# 468323_001_Encoder.net
KiCad netlist of a schematic drawn in Altium Designer
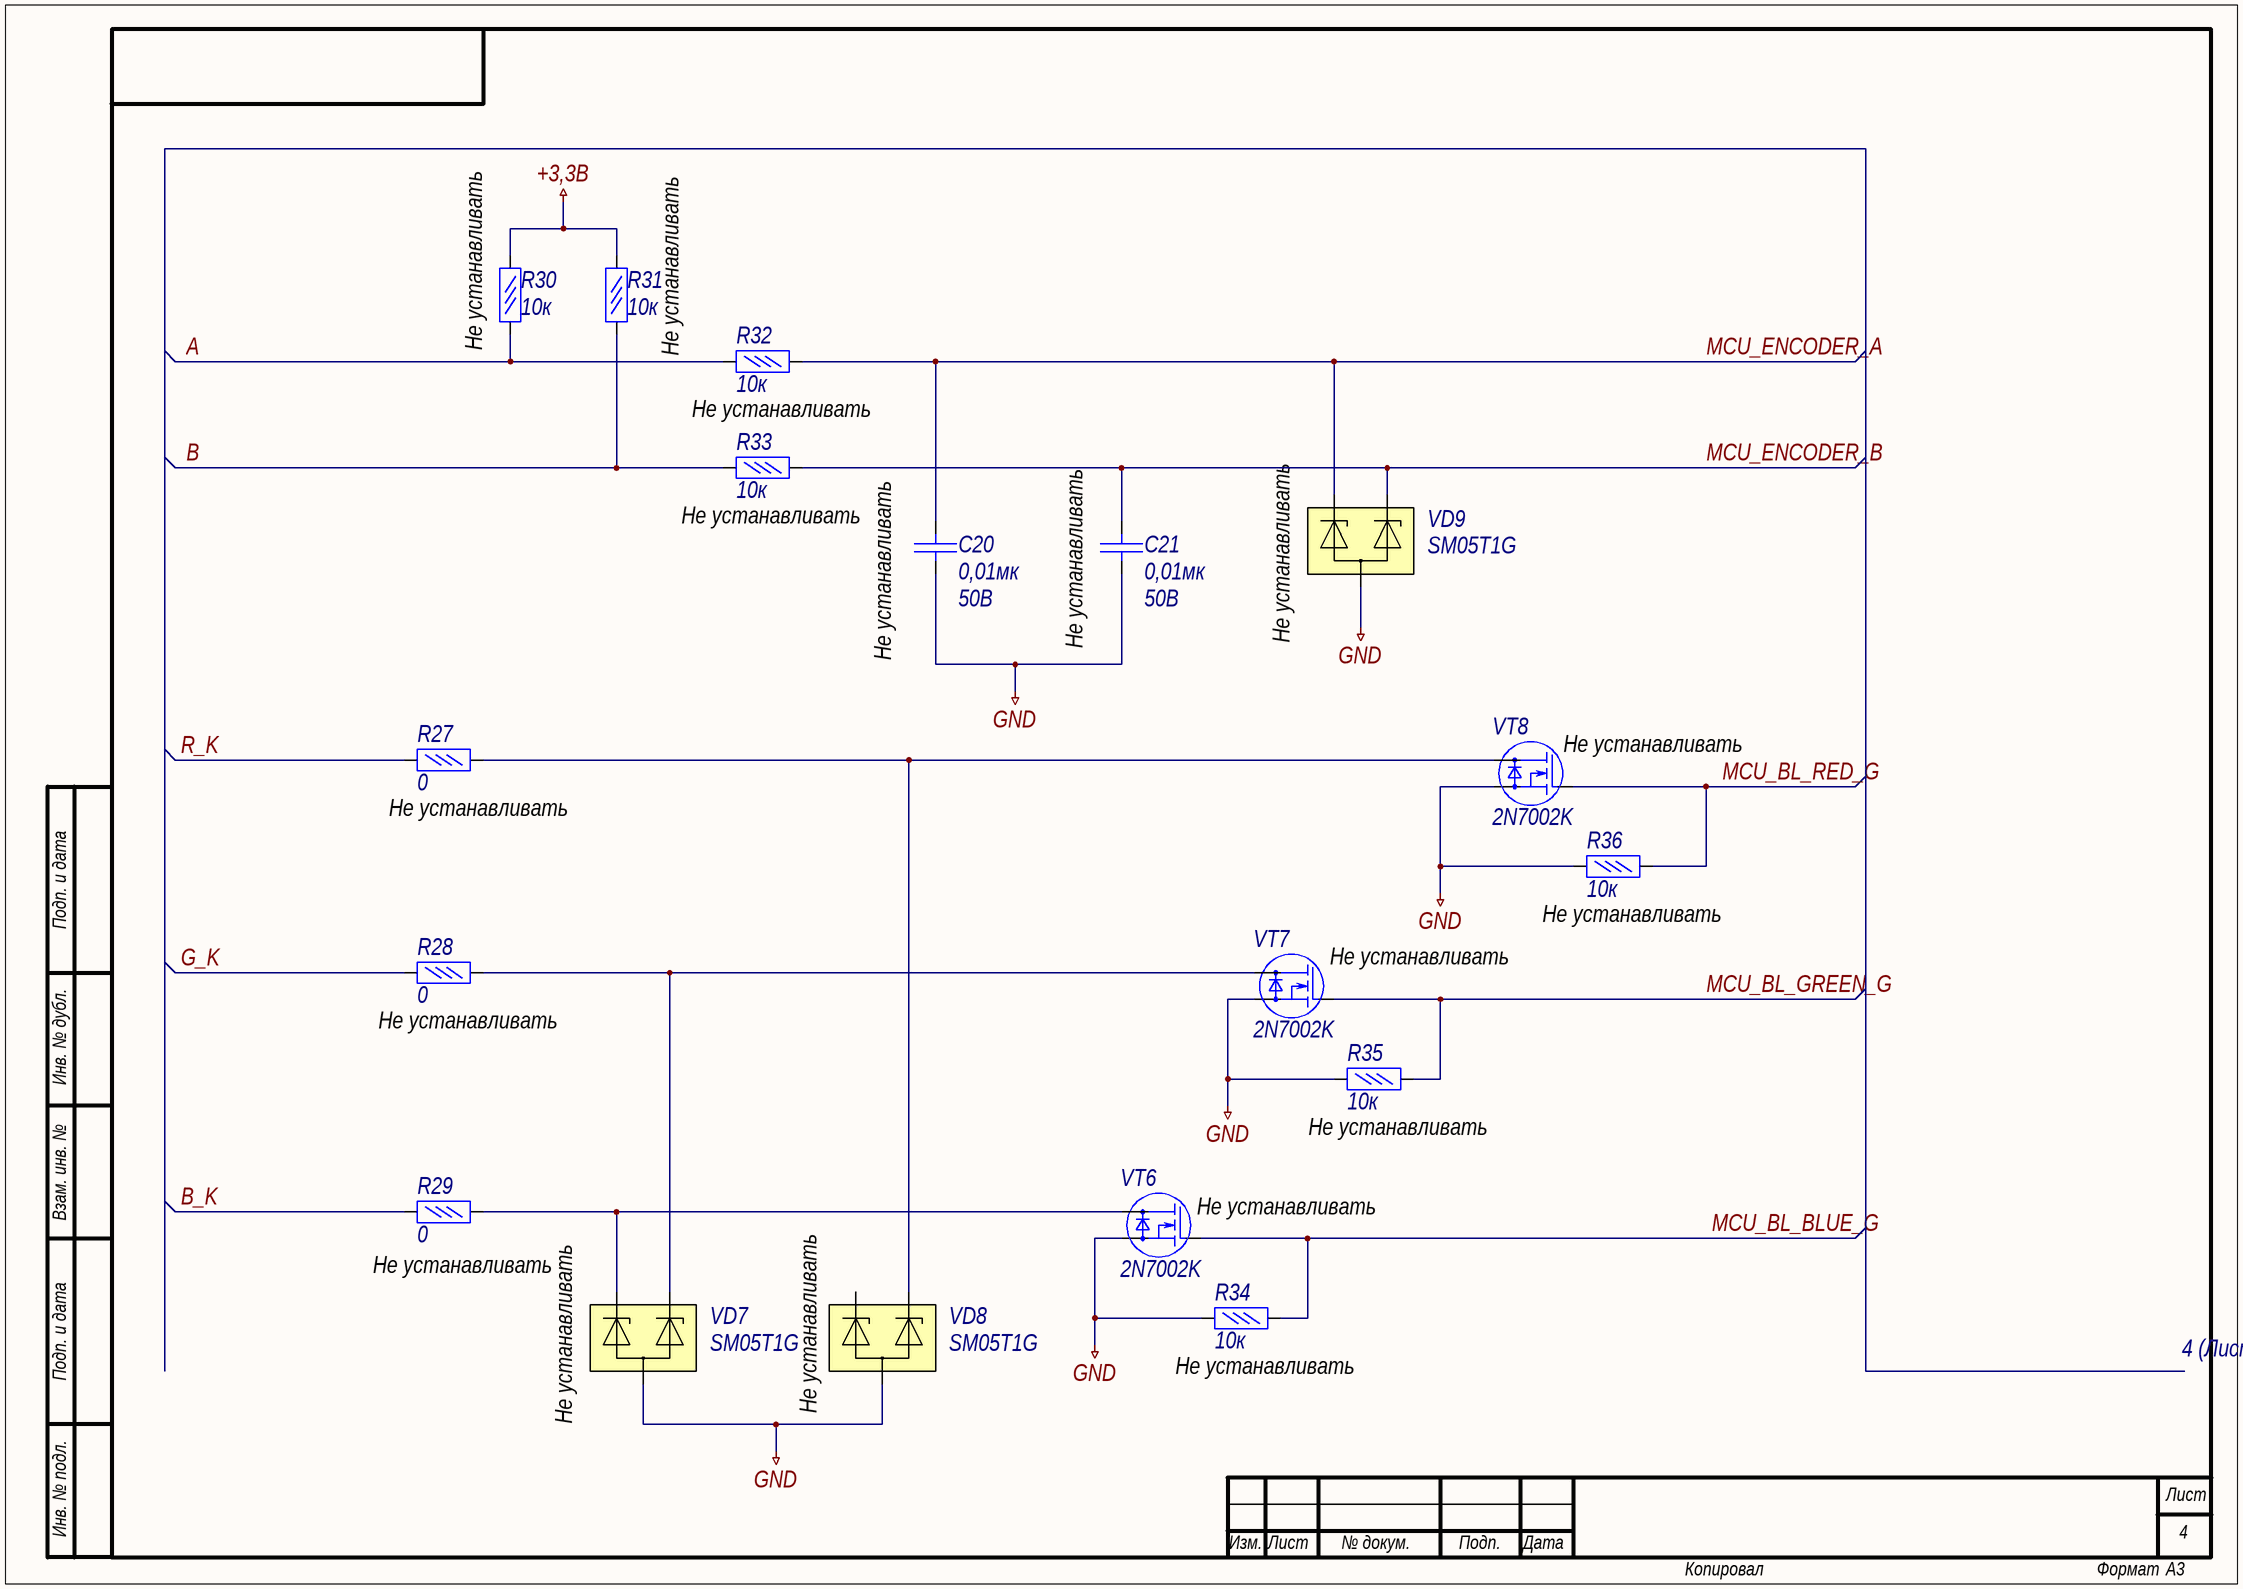
[diagram p0: РЕУН.468323.001_Encoder.SchDoc]

(export (version "E")
  (design (tool "Eeschema 10.0.6"))
  (components
    (comp (ref "C20")
      (value "0,01мк")
      (footprint "C0805_AA")
      (description "Конденсатор кер.")
      (fields (field (name "VOLTAGE") "50В"))
      (libsource (lib "Library_Diana") (part "Конденсатор кер."))
    )
    (comp (ref "C21")
      (value "0,01мк")
      (footprint "C0805_AA")
      (description "Конденсатор кер.")
      (fields (field (name "VOLTAGE") "50В"))
      (libsource (lib "Library_Diana") (part "Конденсатор кер."))
    )
    (comp (ref "R27")
      (value "0")
      (footprint "R1206")
      (description "Резистор 0,05Вт")
      (libsource (lib "Library_Diana") (part "Резистор  0,05Вт"))
    )
    (comp (ref "R28")
      (value "0")
      (footprint "R1206")
      (description "Резистор 0,05Вт")
      (libsource (lib "Library_Diana") (part "Резистор  0,05Вт"))
    )
    (comp (ref "R29")
      (value "0")
      (footprint "R1206")
      (description "Резистор 0,05Вт")
      (libsource (lib "Library_Diana") (part "Резистор  0,05Вт"))
    )
    (comp (ref "R30")
      (value "10к")
      (footprint "R1206")
      (description "Резистор 0,05Вт")
      (libsource (lib "") (part "Резистор  0,05Вт_1"))
    )
    (comp (ref "R31")
      (value "10к")
      (footprint "R1206")
      (description "Резистор 0,05Вт")
      (libsource (lib "") (part "Резистор  0,05Вт_1"))
    )
    (comp (ref "R32")
      (value "10к")
      (footprint "R1206")
      (description "Резистор 0,05Вт")
      (libsource (lib "Library_Diana") (part "Резистор  0,05Вт"))
    )
    (comp (ref "R33")
      (value "10к")
      (footprint "R1206")
      (description "Резистор 0,05Вт")
      (libsource (lib "Library_Diana") (part "Резистор  0,05Вт"))
    )
    (comp (ref "R34")
      (value "10к")
      (footprint "R1206")
      (description "Резистор 0,05Вт")
      (libsource (lib "Library_Diana") (part "Резистор  0,05Вт"))
    )
    (comp (ref "R35")
      (value "10к")
      (footprint "R1206")
      (description "Резистор 0,05Вт")
      (libsource (lib "Library_Diana") (part "Резистор  0,05Вт"))
    )
    (comp (ref "R36")
      (value "10к")
      (footprint "R1206")
      (description "Резистор 0,05Вт")
      (libsource (lib "Library_Diana") (part "Резистор  0,05Вт"))
    )
    (comp (ref "VD7")
      (value "SM05T1G")
      (description "Сборка TVS-диодов")
      (libsource (lib "Library_Diana") (part "ZenerArray2"))
    )
    (comp (ref "VD8")
      (value "SM05T1G")
      (description "Сборка TVS-диодов")
      (libsource (lib "Library_Diana") (part "ZenerArray2"))
    )
    (comp (ref "VD9")
      (value "SM05T1G")
      (description "Сборка TVS-диодов")
      (libsource (lib "Library_Diana") (part "ZenerArray2"))
    )
    (comp (ref "VT6")
      (value "2N7002K")
      (footprint "SOT:SOT23-3")
      (fields (field (name "NAME") "2N7002K"))
      (libsource (lib "Library_Diana") (part "mosfet-n"))
    )
    (comp (ref "VT7")
      (value "2N7002K")
      (footprint "SOT:SOT23-3")
      (fields (field (name "NAME") "2N7002K"))
      (libsource (lib "Library_Diana") (part "mosfet-n"))
    )
    (comp (ref "VT8")
      (value "2N7002K")
      (footprint "SOT:SOT23-3")
      (fields (field (name "NAME") "2N7002K"))
      (libsource (lib "Library_Diana") (part "mosfet-n"))
    )
  )
  (nets
    (net (code "1") (name "+3,3В") (class "Default")
      (node (ref "R30") (pin "2") (pinfunction "2_2") (pintype "passive"))
      (node (ref "R31") (pin "2") (pinfunction "2_2") (pintype "passive"))
    )
    (net (code "2") (name "/A") (class "Default")
      (node (ref "R30") (pin "1") (pinfunction "1_1") (pintype "passive"))
      (node (ref "R32") (pin "1") (pinfunction "1_1") (pintype "passive"))
    )
    (net (code "3") (name "/B") (class "Default")
      (node (ref "R31") (pin "1") (pinfunction "1_1") (pintype "passive"))
      (node (ref "R33") (pin "1") (pinfunction "1_1") (pintype "passive"))
    )
    (net (code "4") (name "/B_K") (class "Default")
      (node (ref "R29") (pin "1") (pinfunction "1_1") (pintype "passive"))
    )
    (net (code "5") (name "/G_K") (class "Default")
      (node (ref "R28") (pin "1") (pinfunction "1_1") (pintype "passive"))
    )
    (net (code "6") (name "/MCU_BL_BLUE_G") (class "Default")
      (node (ref "R34") (pin "2") (pinfunction "2_2") (pintype "passive"))
      (node (ref "VT6") (pin "1") (pinfunction "G_1") (pintype "passive"))
    )
    (net (code "7") (name "/MCU_BL_GREEN_G") (class "Default")
      (node (ref "R35") (pin "2") (pinfunction "2_2") (pintype "passive"))
      (node (ref "VT7") (pin "1") (pinfunction "G_1") (pintype "passive"))
    )
    (net (code "8") (name "/MCU_BL_RED_G") (class "Default")
      (node (ref "R36") (pin "2") (pinfunction "2_2") (pintype "passive"))
      (node (ref "VT8") (pin "1") (pinfunction "G_1") (pintype "passive"))
    )
    (net (code "9") (name "/MCU_ENCODER_A") (class "Default")
      (node (ref "C20") (pin "2") (pinfunction "2_2") (pintype "passive"))
      (node (ref "R32") (pin "2") (pinfunction "2_2") (pintype "passive"))
      (node (ref "VD9") (pin "1") (pintype "passive"))
    )
    (net (code "10") (name "/MCU_ENCODER_B") (class "Default")
      (node (ref "C21") (pin "2") (pinfunction "2_2") (pintype "passive"))
      (node (ref "R33") (pin "2") (pinfunction "2_2") (pintype "passive"))
      (node (ref "VD9") (pin "2") (pintype "passive"))
    )
    (net (code "11") (name "/R_K") (class "Default")
      (node (ref "R27") (pin "1") (pinfunction "1_1") (pintype "passive"))
    )
    (net (code "12") (name "GND") (class "Default")
      (node (ref "C20") (pin "1") (pinfunction "1_1") (pintype "passive"))
      (node (ref "C21") (pin "1") (pinfunction "1_1") (pintype "passive"))
      (node (ref "R34") (pin "1") (pinfunction "1_1") (pintype "passive"))
      (node (ref "R35") (pin "1") (pinfunction "1_1") (pintype "passive"))
      (node (ref "R36") (pin "1") (pinfunction "1_1") (pintype "passive"))
      (node (ref "VD7") (pin "3") (pintype "passive"))
      (node (ref "VD8") (pin "3") (pintype "passive"))
      (node (ref "VD9") (pin "3") (pintype "passive"))
      (node (ref "VT6") (pin "2") (pinfunction "S_2") (pintype "passive"))
      (node (ref "VT7") (pin "2") (pinfunction "S_2") (pintype "passive"))
      (node (ref "VT8") (pin "2") (pinfunction "S_2") (pintype "passive"))
    )
    (net (code "13") (name "Net-(VT6-D)") (class "Default")
      (node (ref "R29") (pin "2") (pinfunction "2_2") (pintype "passive"))
      (node (ref "VD7") (pin "1") (pintype "passive"))
      (node (ref "VT6") (pin "3") (pinfunction "D_3") (pintype "passive"))
    )
    (net (code "14") (name "Net-(VT7-D)") (class "Default")
      (node (ref "R28") (pin "2") (pinfunction "2_2") (pintype "passive"))
      (node (ref "VD7") (pin "2") (pintype "passive"))
      (node (ref "VT7") (pin "3") (pinfunction "D_3") (pintype "passive"))
    )
    (net (code "15") (name "Net-(VT8-D)") (class "Default")
      (node (ref "R27") (pin "2") (pinfunction "2_2") (pintype "passive"))
      (node (ref "VD8") (pin "2") (pintype "passive"))
      (node (ref "VT8") (pin "3") (pinfunction "D_3") (pintype "passive"))
    )
    (net (code "16") (name "unconnected-(VD8-Pad1)") (class "Default")
      (node (ref "VD8") (pin "1") (pintype "passive"))
    )
  )
)
